# SHIELD3.net
KiCad netlist of a schematic drawn in Altium Designer
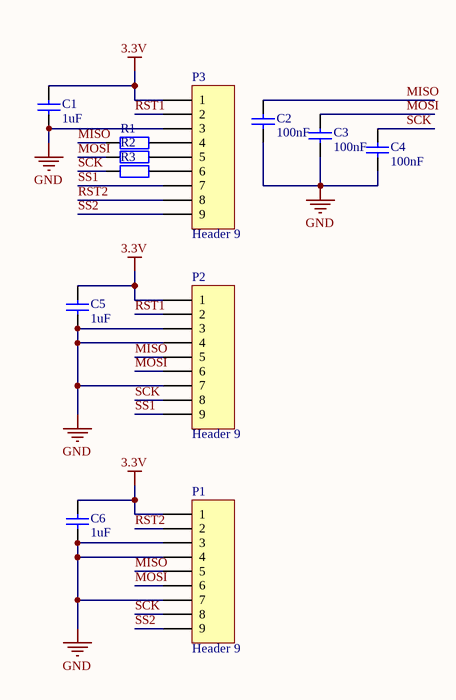
[diagram p0: SHIELD3.SchDoc]

(export (version "E")
  (design (tool "Eeschema 10.0.6"))
  (components
    (comp (ref "C1")
      (value "1uF")
      (footprint "C0805")
      (description "Capacitor")
      (fields (field (name "Comment") "Cap") (field (name "PUBLISHER") "Altium Limited"))
      (libsource (lib "Library") (part "Cap"))
    )
    (comp (ref "C2")
      (value "100nF")
      (footprint "C0805")
      (description "Capacitor")
      (fields (field (name "Comment") "Cap") (field (name "PUBLISHER") "Altium Limited"))
      (libsource (lib "Library") (part "Cap"))
    )
    (comp (ref "C3")
      (value "100nF")
      (footprint "C0805")
      (description "Capacitor")
      (fields (field (name "Comment") "Cap") (field (name "PUBLISHER") "Altium Limited"))
      (libsource (lib "Library") (part "Cap"))
    )
    (comp (ref "C4")
      (value "100nF")
      (footprint "C0805")
      (description "Capacitor")
      (fields (field (name "Comment") "Cap") (field (name "PUBLISHER") "Altium Limited"))
      (libsource (lib "Library") (part "Cap"))
    )
    (comp (ref "C5")
      (value "1uF")
      (footprint "C0805")
      (description "Capacitor")
      (fields (field (name "Comment") "Cap") (field (name "PUBLISHER") "Altium Limited"))
      (libsource (lib "Library") (part "Cap"))
    )
    (comp (ref "C6")
      (value "1uF")
      (footprint "C0805")
      (description "Capacitor")
      (fields (field (name "Comment") "Cap") (field (name "PUBLISHER") "Altium Limited"))
      (libsource (lib "Library") (part "Cap"))
    )
    (comp (ref "P1")
      (value "Header 9")
      (footprint "HDR1X9")
      (description "Header, 9-Pin")
      (fields (field (name "PUBLISHER") "Altium Limited"))
      (libsource (lib "Miscellaneous Connectors") (part "Header 9"))
    )
    (comp (ref "P2")
      (value "Header 9")
      (footprint "HDR1X9")
      (description "Header, 9-Pin")
      (fields (field (name "PUBLISHER") "Altium Limited"))
      (libsource (lib "Miscellaneous Connectors") (part "Header 9"))
    )
    (comp (ref "P3")
      (value "Header 9")
      (footprint "HDR1X9")
      (description "Header, 9-Pin")
      (fields (field (name "PUBLISHER") "Altium Limited"))
      (libsource (lib "Miscellaneous Connectors") (part "Header 9"))
    )
    (comp (ref "R1")
      (value "Res2")
      (footprint "6-0805_N")
      (description "Resistor")
      (fields (field (name "PUBLISHER") "Altium Limited"))
      (libsource (lib "Library") (part "Res2"))
    )
    (comp (ref "R2")
      (value "Res2")
      (footprint "6-0805_N")
      (description "Resistor")
      (fields (field (name "PUBLISHER") "Altium Limited"))
      (libsource (lib "Library") (part "Res2"))
    )
    (comp (ref "R3")
      (value "Res2")
      (footprint "6-0805_N")
      (description "Resistor")
      (fields (field (name "PUBLISHER") "Altium Limited"))
      (libsource (lib "Library") (part "Res2"))
    )
  )
  (nets
    (net (code "1") (name "/MISO") (class "Default")
      (node (ref "C2") (pin "2") (pinfunction "2_2") (pintype "passive"))
      (node (ref "P1") (pin "5") (pinfunction "5_5") (pintype "passive"))
      (node (ref "P2") (pin "5") (pinfunction "5_5") (pintype "passive"))
      (node (ref "R1") (pin "1") (pinfunction "1_1") (pintype "passive"))
    )
    (net (code "2") (name "/MOSI") (class "Default")
      (node (ref "C3") (pin "1") (pinfunction "1_1") (pintype "passive"))
      (node (ref "P1") (pin "6") (pinfunction "6_6") (pintype "passive"))
      (node (ref "P2") (pin "6") (pinfunction "6_6") (pintype "passive"))
      (node (ref "R2") (pin "1") (pinfunction "1_1") (pintype "passive"))
    )
    (net (code "3") (name "/RST1") (class "Default")
      (node (ref "P2") (pin "2") (pinfunction "2_2") (pintype "passive"))
      (node (ref "P3") (pin "2") (pinfunction "2_2") (pintype "passive"))
    )
    (net (code "4") (name "/RST2") (class "Default")
      (node (ref "P1") (pin "2") (pinfunction "2_2") (pintype "passive"))
      (node (ref "P3") (pin "8") (pinfunction "8_8") (pintype "passive"))
    )
    (net (code "5") (name "/SCK") (class "Default")
      (node (ref "C4") (pin "1") (pinfunction "1_1") (pintype "passive"))
      (node (ref "P1") (pin "8") (pinfunction "8_8") (pintype "passive"))
      (node (ref "P2") (pin "8") (pinfunction "8_8") (pintype "passive"))
      (node (ref "R3") (pin "1") (pinfunction "1_1") (pintype "passive"))
    )
    (net (code "6") (name "/SS1") (class "Default")
      (node (ref "P2") (pin "9") (pinfunction "9_9") (pintype "passive"))
      (node (ref "P3") (pin "7") (pinfunction "7_7") (pintype "passive"))
    )
    (net (code "7") (name "/SS2") (class "Default")
      (node (ref "P1") (pin "9") (pinfunction "9_9") (pintype "passive"))
      (node (ref "P3") (pin "9") (pinfunction "9_9") (pintype "passive"))
    )
    (net (code "8") (name "3.3V") (class "Default")
      (node (ref "C1") (pin "2") (pinfunction "2_2") (pintype "passive"))
      (node (ref "C5") (pin "2") (pinfunction "2_2") (pintype "passive"))
      (node (ref "C6") (pin "2") (pinfunction "2_2") (pintype "passive"))
      (node (ref "P1") (pin "1") (pinfunction "1_1") (pintype "passive"))
      (node (ref "P2") (pin "1") (pinfunction "1_1") (pintype "passive"))
      (node (ref "P3") (pin "1") (pinfunction "1_1") (pintype "passive"))
    )
    (net (code "9") (name "GND") (class "Default")
      (node (ref "C1") (pin "1") (pinfunction "1_1") (pintype "passive"))
      (node (ref "C2") (pin "1") (pinfunction "1_1") (pintype "passive"))
      (node (ref "C3") (pin "2") (pinfunction "2_2") (pintype "passive"))
      (node (ref "C4") (pin "2") (pinfunction "2_2") (pintype "passive"))
      (node (ref "C5") (pin "1") (pinfunction "1_1") (pintype "passive"))
      (node (ref "C6") (pin "1") (pinfunction "1_1") (pintype "passive"))
      (node (ref "P1") (pin "3") (pinfunction "3_3") (pintype "passive"))
      (node (ref "P1") (pin "4") (pinfunction "4_4") (pintype "passive"))
      (node (ref "P1") (pin "7") (pinfunction "7_7") (pintype "passive"))
      (node (ref "P2") (pin "3") (pinfunction "3_3") (pintype "passive"))
      (node (ref "P2") (pin "4") (pinfunction "4_4") (pintype "passive"))
      (node (ref "P2") (pin "7") (pinfunction "7_7") (pintype "passive"))
      (node (ref "P3") (pin "3") (pinfunction "3_3") (pintype "passive"))
    )
    (net (code "10") (name "Net-(P3-Pad4)") (class "Default")
      (node (ref "P3") (pin "4") (pinfunction "4_4") (pintype "passive"))
      (node (ref "R1") (pin "2") (pinfunction "2_2") (pintype "passive"))
    )
    (net (code "11") (name "Net-(P3-Pad5)") (class "Default")
      (node (ref "P3") (pin "5") (pinfunction "5_5") (pintype "passive"))
      (node (ref "R2") (pin "2") (pinfunction "2_2") (pintype "passive"))
    )
    (net (code "12") (name "Net-(P3-Pad6)") (class "Default")
      (node (ref "P3") (pin "6") (pinfunction "6_6") (pintype "passive"))
      (node (ref "R3") (pin "2") (pinfunction "2_2") (pintype "passive"))
    )
  )
)
